# PIBSchematic.net
KiCad netlist of a schematic drawn in Altium Designer
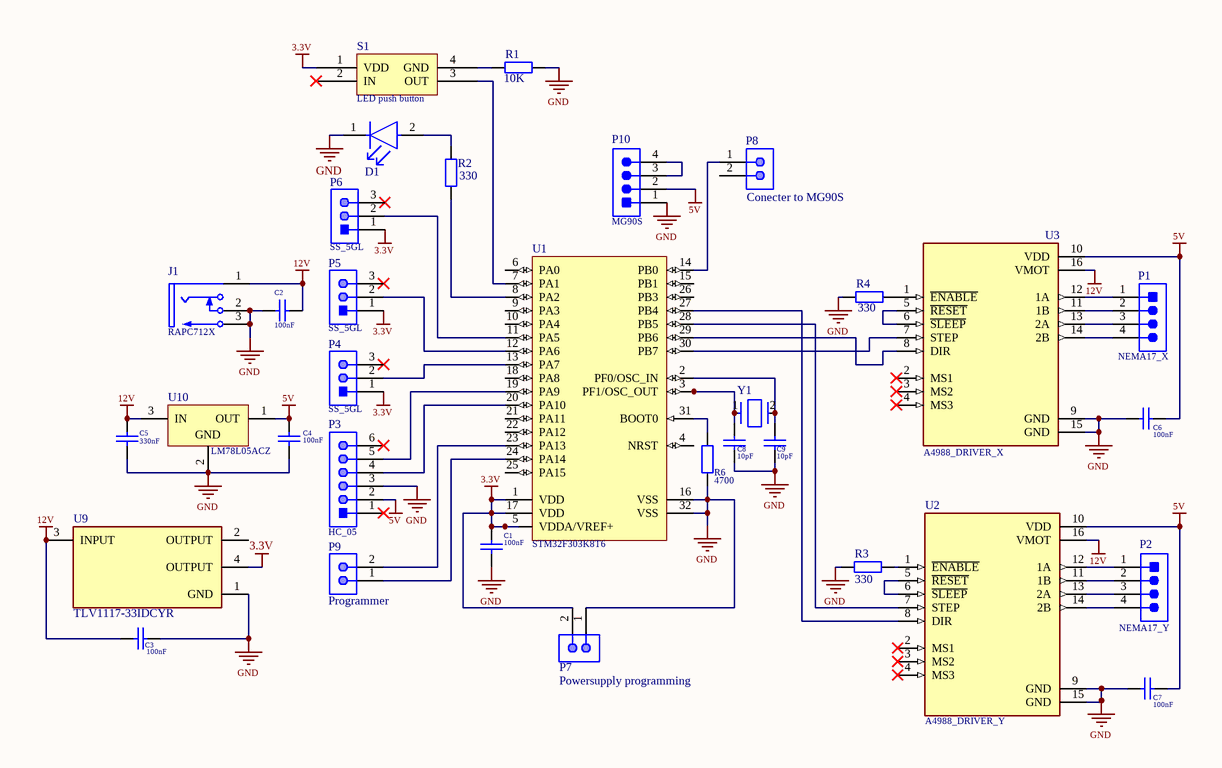
[diagram p0: PIBSchematic.SchDoc]

(export (version "E")
  (design (tool "Eeschema 10.0.6"))
  (components
    (comp (ref "C1")
      (value "100nF")
      (footprint "KEMT-1206-2_M")
      (description "CAP, Ceramic, 0.1 uF, +/- 10%, 50 V, -55 to 125 degC, 1206 (3216 Metric), RoHS, Tape and Reel")
      (fields (field (name "MANUFACTURER") "Kemet"))
      (libsource (lib "Altium Content Vault") (part "CAP-NP-2"))
    )
    (comp (ref "C2")
      (value "100nF")
      (footprint "KEMT-1206-2_M")
      (description "CAP, Ceramic, 0.1 uF, +/- 10%, 50 V, -55 to 125 degC, 1206 (3216 Metric), RoHS, Tape and Reel")
      (fields (field (name "MANUFACTURER") "Kemet"))
      (libsource (lib "Altium Content Vault") (part "CAP-NP-2"))
    )
    (comp (ref "C3")
      (value "100nF")
      (footprint "KEMT-1206-2_M")
      (description "CAP, Ceramic, 0.1 uF, +/- 10%, 50 V, -55 to 125 degC, 1206 (3216 Metric), RoHS, Tape and Reel")
      (fields (field (name "MANUFACTURER") "Kemet"))
      (libsource (lib "Altium Content Vault") (part "CAP-NP-2"))
    )
    (comp (ref "C4")
      (value "100nF")
      (footprint "KEMT-1206-2_M")
      (description "CAP, Ceramic, 0.1 uF, +/- 10%, 50 V, -55 to 125 degC, 1206 (3216 Metric), RoHS, Tape and Reel")
      (fields (field (name "MANUFACTURER") "Kemet"))
      (libsource (lib "Altium Content Vault") (part "CAP-NP-2"))
    )
    (comp (ref "C5")
      (value "330nF")
      (footprint "KEMT-1206-2_M")
      (description "CAP, Ceramic, 0.1 uF, +/- 10%, 50 V, -55 to 125 degC, 1206 (3216 Metric), RoHS, Tape and Reel")
      (fields (field (name "MANUFACTURER") "Kemet"))
      (libsource (lib "Altium Content Vault") (part "CAP-NP-2"))
    )
    (comp (ref "C6")
      (value "100nF")
      (footprint "KEMT-1206-2_M")
      (description "CAP, Ceramic, 0.1 uF, +/- 10%, 50 V, -55 to 125 degC, 1206 (3216 Metric), RoHS, Tape and Reel")
      (fields (field (name "MANUFACTURER") "Kemet"))
      (libsource (lib "Altium Content Vault") (part "CAP-NP-2"))
    )
    (comp (ref "C7")
      (value "100nF")
      (footprint "KEMT-1206-2_M")
      (description "CAP, Ceramic, 0.1 uF, +/- 10%, 50 V, -55 to 125 degC, 1206 (3216 Metric), RoHS, Tape and Reel")
      (fields (field (name "MANUFACTURER") "Kemet"))
      (libsource (lib "Altium Content Vault") (part "CAP-NP-2"))
    )
    (comp (ref "C8")
      (value "10pF")
      (footprint "KEMT-1206-2_M")
      (description "CAP, Ceramic, 0.1 uF, +/- 10%, 50 V, -55 to 125 degC, 1206 (3216 Metric), RoHS, Tape and Reel")
      (fields (field (name "MANUFACTURER") "Kemet"))
      (libsource (lib "Altium Content Vault") (part "CAP-NP-2"))
    )
    (comp (ref "C9")
      (value "10pF")
      (footprint "KEMT-1206-2_M")
      (description "CAP, Ceramic, 0.1 uF, +/- 10%, 50 V, -55 to 125 degC, 1206 (3216 Metric), RoHS, Tape and Reel")
      (fields (field (name "MANUFACTURER") "Kemet"))
      (libsource (lib "Altium Content Vault") (part "CAP-NP-2"))
    )
    (comp (ref "D1")
      (value "HLMP-1719")
      (footprint "FP-HLMP-1719-MFG")
      (description "LED YELLOW DIFFUSED T-1 T/H")
      (fields
        (field (name "MANUFACTURER") "Broadcom")
        (field (name "OCTOPART") "https://octopart.com/hlmp-1719-broadcom-71130405")
      )
      (libsource (lib "Altium Content Vault") (part "8706943c75ba83719d021d2fdc84c58"))
    )
    (comp (ref "J1")
      (value "RAPC712X")
      (footprint "SWITCH-RAPC712X-3_V")
      (description "Conn Powerjack Mini R/A PCMT, 5 A, 3-Pin THD, RoHS")
      (fields (field (name "MANUFACTURER") "Switchcraft"))
      (libsource (lib "Altium Content Vault") (part "SWITCH-RAPC712X-3"))
    )
    (comp (ref "P1")
      (value "NEMA17_X")
      (footprint "TECO-640456-4")
      (description "Male Header, Pitch 2.54 mm, 1 x 4 Position, Height 10.03 mm, Tail Length 3.56 mm, RoHS, Bulk")
      (fields (field (name "MANUFACTURER") "TE Connectivity"))
      (libsource (lib "Altium Content Vault") (part "CN-1P-M-R4"))
    )
    (comp (ref "P2")
      (value "NEMA17_Y")
      (footprint "TECO-640456-4")
      (description "Male Header, Pitch 2.54 mm, 1 x 4 Position, Height 10.03 mm, Tail Length 3.56 mm, RoHS, Bulk")
      (fields (field (name "MANUFACTURER") "TE Connectivity"))
      (libsource (lib "Altium Content Vault") (part "CN-1P-M-R4"))
    )
    (comp (ref "P3")
      (value "HC_05")
      (footprint "66200611122")
      (description "THT Male Header WR-MPC3, Vertical, Single Row, pitch 3 mm, 6 pins")
      (fields
        (field (name "MANUFACTURER") "Wurth Elektronik")
        (field (name "PART NUMBER") "66200611122")
        (field (name "PUBLISHER") "WurthElektronik")
      )
      (libsource (lib "Altium Content Vault") (part "WE-CN-1P-M-R6"))
    )
    (comp (ref "P4")
      (value "SS_5GL")
      (footprint "66200311122")
      (description "THT Male Header WR-MPC3, Vertical, Single Row, pitch 3 mm, 3 pins")
      (fields
        (field (name "MANUFACTURER") "Wurth Elektronik")
        (field (name "PART NUMBER") "66200311122")
        (field (name "PUBLISHER") "WurthElektronik")
      )
      (libsource (lib "Altium Content Vault") (part "WE-CN-1P-M-R3"))
    )
    (comp (ref "P5")
      (value "SS_5GL")
      (footprint "66200311122")
      (description "THT Male Header WR-MPC3, Vertical, Single Row, pitch 3 mm, 3 pins")
      (fields
        (field (name "MANUFACTURER") "Wurth Elektronik")
        (field (name "PART NUMBER") "66200311122")
        (field (name "PUBLISHER") "WurthElektronik")
      )
      (libsource (lib "Altium Content Vault") (part "WE-CN-1P-M-R3"))
    )
    (comp (ref "P6")
      (value "SS_5GL")
      (footprint "66200311122")
      (description "THT Male Header WR-MPC3, Vertical, Single Row, pitch 3 mm, 3 pins")
      (fields
        (field (name "MANUFACTURER") "Wurth Elektronik")
        (field (name "PART NUMBER") "66200311122")
        (field (name "PUBLISHER") "WurthElektronik")
      )
      (libsource (lib "Altium Content Vault") (part "WE-CN-1P-M-R3"))
    )
    (comp (ref "P7")
      (value "Powersupply programming")
      (footprint "TECO-5-146280-2_V")
      (fields (field (name "MANUFACTURER") "TE Connectivity"))
      (libsource (lib "Altium Content Vault") (part "CN-1P-M-R2"))
    )
    (comp (ref "P8")
      (value "Conecter to MG90S")
      (footprint "TECO-5-146280-2_V")
      (fields (field (name "MANUFACTURER") "TE Connectivity"))
      (libsource (lib "") (part "CN-1P-M-R2_1"))
    )
    (comp (ref "P9")
      (value "Programmer")
      (footprint "TECO-5-146280-2_V")
      (fields (field (name "MANUFACTURER") "TE Connectivity"))
      (libsource (lib "") (part "CN-1P-M-R2_2"))
    )
    (comp (ref "P10")
      (value "MG90S")
      (footprint "TECO-640456-4")
      (description "Male Header, Pitch 2.54 mm, 1 x 4 Position, Height 10.03 mm, Tail Length 3.56 mm, RoHS, Bulk")
      (fields (field (name "MANUFACTURER") "TE Connectivity"))
      (libsource (lib "") (part "CN-1P-M-R4_1"))
    )
    (comp (ref "R1")
      (value "10K")
      (footprint "AXIAL-0.4")
      (description "Resistor")
      (fields (field (name "Comment") "Res2") (field (name "PUBLISHER") "Altium Limited"))
      (libsource (lib "") (part "Res2_1"))
    )
    (comp (ref "R2")
      (value "330")
      (footprint "AXIAL-0.4")
      (description "Resistor")
      (fields (field (name "Comment") "Res2") (field (name "PUBLISHER") "Altium Limited"))
      (libsource (lib "Miscellaneous Devices") (part "Res2"))
    )
    (comp (ref "R3")
      (value "330")
      (footprint "AXIAL-0.4")
      (description "Resistor")
      (fields (field (name "Comment") "Res2") (field (name "PUBLISHER") "Altium Limited"))
      (libsource (lib "") (part "Res2_1"))
    )
    (comp (ref "R4")
      (value "330")
      (footprint "AXIAL-0.4")
      (description "Resistor")
      (fields (field (name "Comment") "Res2") (field (name "PUBLISHER") "Altium Limited"))
      (libsource (lib "") (part "Res2_1"))
    )
    (comp (ref "R6")
      (value "4700")
      (footprint "AXIAL-0.4")
      (description "Resistor")
      (fields (field (name "Comment") "Res2") (field (name "PUBLISHER") "Altium Limited"))
      (libsource (lib "Miscellaneous Devices") (part "Res2"))
    )
    (comp (ref "S1")
      (value "LED push button")
      (footprint "LED push button PcbLib1:PCBComponent_1")
      (libsource (lib "LED push button") (part "LED push button"))
    )
    (comp (ref "U1")
      (value "STM32F303K8T6")
      (footprint "STM-LQFP32_M")
      (libsource (lib "Altium Content Vault") (part "MC-ARM-STM32F303-LQFP32"))
    )
    (comp (ref "U2")
      (value "A4988_DRIVER_Y")
      (footprint "MODULE_A4988_STEPPER_MOTOR_DRIVER_CARRIER")
      (description "Stepper Motor Driver")
      (fields (field (name "MP") "A4988 STEPPER MOTOR DRIVER CARRIER") (field (name "MF") "Pololu"))
      (libsource (lib "A4988_STEPPER_MOTOR_DRIVER_CARRIER") (part "A4988_STEPPER_MOTOR_DRIVER_CARRIER"))
    )
    (comp (ref "U3")
      (value "A4988_DRIVER_X")
      (footprint "MODULE_A4988_STEPPER_MOTOR_DRIVER_CARRIER")
      (description "Stepper Motor Driver")
      (fields (field (name "MP") "A4988 STEPPER MOTOR DRIVER CARRIER") (field (name "MF") "Pololu"))
      (libsource (lib "A4988_STEPPER_MOTOR_DRIVER_CARRIER") (part "A4988_STEPPER_MOTOR_DRIVER_CARRIER"))
    )
    (comp (ref "U9")
      (value "TLV1117-33IDCYR")
      (footprint "FP-DCY0004A-MFG")
      (description "IC REG LIN 3.3V 800MA SOT223-4")
      (fields
        (field (name "MANUFACTURER") "Texas Instruments")
        (field (name "OCTOPART") "https://octopart.com/tlv1117-33idcyr-texas+instruments-669250")
      )
      (libsource (lib "Altium Content Vault") (part "d420fb9686013fb832e66295cdf4acf"))
    )
    (comp (ref "U10")
      (value "LM78L05ACZ")
      (footprint "LP0003A")
      (description "3-Terminal Positive Regulator, 5 Vout, 3-pin TO-92, Pb-Free")
      (fields (field (name "PARTNUMBER") "LM78L05ACZ/NOPB") (field (name "MANUFACTURER") "Texas Instruments"))
      (libsource (lib "Altium Content Vault") (part "PM-REG-LM78L05-SIL3"))
    )
    (comp (ref "Y1")
      (value "ABLS2-8.000MHZ-D4Y-T")
      (footprint "FP-ABLS2-MFG")
      (description "CRYSTAL 8.0000MHZ 18PF SMD")
      (fields (field (name "TOLERANCE") "30ppm"))
      (libsource (lib "Altium Content Vault") (part "c23a69dc6c9e2f18f2079038eb95dd1"))
    )
  )
  (nets
    (net (code "1") (name "3.3V") (class "Default")
      (node (ref "C1") (pin "2") (pinfunction "2_2") (pintype "passive"))
      (node (ref "P4") (pin "1") (pinfunction "1_1") (pintype "passive"))
      (node (ref "P5") (pin "1") (pinfunction "1_1") (pintype "passive"))
      (node (ref "P6") (pin "1") (pinfunction "1_1") (pintype "passive"))
      (node (ref "P7") (pin "2") (pinfunction "2_2") (pintype "passive"))
      (node (ref "S1") (pin "1") (pinfunction "VDD_1") (pintype "passive"))
      (node (ref "U1") (pin "1") (pinfunction "VDD_1") (pintype "power_in"))
      (node (ref "U1") (pin "17") (pinfunction "VDD_17") (pintype "power_in"))
      (node (ref "U1") (pin "5") (pinfunction "VDDA/VREF+_5") (pintype "power_in"))
      (node (ref "U9") (pin "4") (pinfunction "OUTPUT_4") (pintype "power_in"))
    )
    (net (code "2") (name "5V") (class "Default")
      (node (ref "C4") (pin "1") (pinfunction "1_1") (pintype "passive"))
      (node (ref "C6") (pin "1") (pinfunction "1_1") (pintype "passive"))
      (node (ref "C7") (pin "1") (pinfunction "1_1") (pintype "passive"))
      (node (ref "P10") (pin "2") (pinfunction "2_2") (pintype "passive"))
      (node (ref "P3") (pin "2") (pinfunction "2_2") (pintype "passive"))
      (node (ref "U10") (pin "1") (pinfunction "OUT_1") (pintype "power_in"))
      (node (ref "U2") (pin "10") (pinfunction "VDD_10") (pintype "power_in"))
      (node (ref "U3") (pin "10") (pinfunction "VDD_10") (pintype "power_in"))
    )
    (net (code "3") (name "12V") (class "Default")
      (node (ref "C2") (pin "2") (pinfunction "2_2") (pintype "passive"))
      (node (ref "C3") (pin "2") (pinfunction "2_2") (pintype "passive"))
      (node (ref "C5") (pin "2") (pinfunction "2_2") (pintype "passive"))
      (node (ref "J1") (pin "1") (pinfunction "1_1") (pintype "passive"))
      (node (ref "U10") (pin "3") (pinfunction "IN_3") (pintype "power_in"))
      (node (ref "U2") (pin "16") (pinfunction "VMOT_16") (pintype "power_in"))
      (node (ref "U3") (pin "16") (pinfunction "VMOT_16") (pintype "power_in"))
      (node (ref "U9") (pin "3") (pinfunction "INPUT_3") (pintype "power_in"))
    )
    (net (code "4") (name "GND") (class "Default")
      (node (ref "C1") (pin "1") (pinfunction "1_1") (pintype "passive"))
      (node (ref "C2") (pin "1") (pinfunction "1_1") (pintype "passive"))
      (node (ref "C3") (pin "1") (pinfunction "1_1") (pintype "passive"))
      (node (ref "C4") (pin "2") (pinfunction "2_2") (pintype "passive"))
      (node (ref "C5") (pin "1") (pinfunction "1_1") (pintype "passive"))
      (node (ref "C6") (pin "2") (pinfunction "2_2") (pintype "passive"))
      (node (ref "C7") (pin "2") (pinfunction "2_2") (pintype "passive"))
      (node (ref "C8") (pin "2") (pinfunction "2_2") (pintype "passive"))
      (node (ref "C9") (pin "2") (pinfunction "2_2") (pintype "passive"))
      (node (ref "D1") (pin "1") (pinfunction "C_1") (pintype "passive"))
      (node (ref "J1") (pin "2") (pinfunction "2_2") (pintype "passive"))
      (node (ref "J1") (pin "3") (pinfunction "3_3") (pintype "passive"))
      (node (ref "P10") (pin "1") (pinfunction "1_1") (pintype "passive"))
      (node (ref "P3") (pin "3") (pinfunction "3_3") (pintype "passive"))
      (node (ref "P7") (pin "1") (pinfunction "1_1") (pintype "passive"))
      (node (ref "R1") (pin "2") (pinfunction "2_2") (pintype "passive"))
      (node (ref "R3") (pin "1") (pinfunction "1_1") (pintype "passive"))
      (node (ref "R4") (pin "1") (pinfunction "1_1") (pintype "passive"))
      (node (ref "R6") (pin "1") (pinfunction "1_1") (pintype "passive"))
      (node (ref "U1") (pin "16") (pinfunction "VSS_16") (pintype "power_in"))
      (node (ref "U1") (pin "32") (pinfunction "VSS_32") (pintype "power_in"))
      (node (ref "U10") (pin "2") (pinfunction "GND_2") (pintype "power_in"))
      (node (ref "U2") (pin "15") (pinfunction "GND_15") (pintype "power_in"))
      (node (ref "U2") (pin "9") (pinfunction "GND_9") (pintype "power_in"))
      (node (ref "U3") (pin "15") (pinfunction "GND_15") (pintype "power_in"))
      (node (ref "U3") (pin "9") (pinfunction "GND_9") (pintype "power_in"))
      (node (ref "U9") (pin "1") (pinfunction "GND_1") (pintype "power_in"))
    )
    (net (code "5") (name "Net-(D1-A)") (class "Default")
      (node (ref "D1") (pin "2") (pinfunction "A_2") (pintype "passive"))
      (node (ref "R2") (pin "2") (pinfunction "2_2") (pintype "passive"))
    )
    (net (code "6") (name "Net-(P10-Pad3)") (class "Default")
      (node (ref "P10") (pin "3") (pinfunction "3_3") (pintype "passive"))
      (node (ref "P10") (pin "4") (pinfunction "4_4") (pintype "passive"))
    )
    (net (code "7") (name "Net-(S1-GND)") (class "Default")
      (node (ref "R1") (pin "1") (pinfunction "1_1") (pintype "passive"))
      (node (ref "S1") (pin "4") (pinfunction "GND_4") (pintype "passive"))
    )
    (net (code "8") (name "Net-(S1-OUT)") (class "Default")
      (node (ref "S1") (pin "3") (pinfunction "OUT_3") (pintype "passive"))
      (node (ref "U1") (pin "7") (pinfunction "PA1_7") (pintype "bidirectional"))
    )
    (net (code "9") (name "Net-(U1-BOOT0)") (class "Default")
      (node (ref "R6") (pin "2") (pinfunction "2_2") (pintype "passive"))
      (node (ref "U1") (pin "31") (pinfunction "BOOT0_31") (pintype "input"))
    )
    (net (code "10") (name "Net-(U1-PA2)") (class "Default")
      (node (ref "R2") (pin "1") (pinfunction "1_1") (pintype "passive"))
      (node (ref "U1") (pin "8") (pinfunction "PA2_8") (pintype "bidirectional"))
    )
    (net (code "11") (name "Net-(U1-PA5)") (class "Default")
      (node (ref "P6") (pin "2") (pinfunction "2_2") (pintype "passive"))
      (node (ref "U1") (pin "11") (pinfunction "PA5_11") (pintype "bidirectional"))
    )
    (net (code "12") (name "Net-(U1-PA6)") (class "Default")
      (node (ref "P5") (pin "2") (pinfunction "2_2") (pintype "passive"))
      (node (ref "U1") (pin "12") (pinfunction "PA6_12") (pintype "bidirectional"))
    )
    (net (code "13") (name "Net-(U1-PA7)") (class "Default")
      (node (ref "P4") (pin "2") (pinfunction "2_2") (pintype "passive"))
      (node (ref "U1") (pin "13") (pinfunction "PA7_13") (pintype "bidirectional"))
    )
    (net (code "14") (name "Net-(U1-PA9)") (class "Default")
      (node (ref "P3") (pin "5") (pinfunction "5_5") (pintype "passive"))
      (node (ref "U1") (pin "19") (pinfunction "PA9_19") (pintype "bidirectional"))
    )
    (net (code "15") (name "Net-(U1-PA10)") (class "Default")
      (node (ref "P3") (pin "4") (pinfunction "4_4") (pintype "passive"))
      (node (ref "U1") (pin "20") (pinfunction "PA10_20") (pintype "bidirectional"))
    )
    (net (code "16") (name "Net-(U1-PA13)") (class "Default")
      (node (ref "P9") (pin "2") (pinfunction "2_2") (pintype "passive"))
      (node (ref "U1") (pin "23") (pinfunction "PA13_23") (pintype "bidirectional"))
    )
    (net (code "17") (name "Net-(U1-PA14)") (class "Default")
      (node (ref "P9") (pin "1") (pinfunction "1_1") (pintype "passive"))
      (node (ref "U1") (pin "24") (pinfunction "PA14_24") (pintype "bidirectional"))
    )
    (net (code "18") (name "Net-(U1-PB0)") (class "Default")
      (node (ref "P8") (pin "1") (pinfunction "1_1") (pintype "passive"))
      (node (ref "U1") (pin "14") (pinfunction "PB0_14") (pintype "bidirectional"))
    )
    (net (code "19") (name "Net-(U1-PB4)") (class "Default")
      (node (ref "U1") (pin "27") (pinfunction "PB4_27") (pintype "bidirectional"))
      (node (ref "U2") (pin "8") (pinfunction "DIR_8") (pintype "input"))
    )
    (net (code "20") (name "Net-(U1-PB5)") (class "Default")
      (node (ref "U1") (pin "28") (pinfunction "PB5_28") (pintype "bidirectional"))
      (node (ref "U2") (pin "7") (pinfunction "STEP_7") (pintype "input"))
    )
    (net (code "21") (name "Net-(U1-PB6)") (class "Default")
      (node (ref "U1") (pin "29") (pinfunction "PB6_29") (pintype "bidirectional"))
      (node (ref "U3") (pin "8") (pinfunction "DIR_8") (pintype "input"))
    )
    (net (code "22") (name "Net-(U1-PB7)") (class "Default")
      (node (ref "U1") (pin "30") (pinfunction "PB7_30") (pintype "bidirectional"))
      (node (ref "U3") (pin "7") (pinfunction "STEP_7") (pintype "input"))
    )
    (net (code "23") (name "Net-(U1-PF0{slash}OSC_IN)") (class "Default")
      (node (ref "C9") (pin "1") (pinfunction "1_1") (pintype "passive"))
      (node (ref "U1") (pin "2") (pinfunction "PF0/OSC_IN_2") (pintype "bidirectional"))
      (node (ref "Y1") (pin "2") (pinfunction "2_2") (pintype "passive"))
    )
    (net (code "24") (name "Net-(U1-PF1{slash}OSC_OUT)") (class "Default")
      (node (ref "C8") (pin "1") (pinfunction "1_1") (pintype "passive"))
      (node (ref "U1") (pin "3") (pinfunction "PF1/OSC_OUT_3") (pintype "bidirectional"))
      (node (ref "Y1") (pin "1") (pinfunction "1_1") (pintype "passive"))
    )
    (net (code "25") (name "Net-(U2-1A)") (class "Default")
      (node (ref "P2") (pin "1") (pinfunction "1_1") (pintype "passive"))
      (node (ref "U2") (pin "12") (pinfunction "1A_12") (pintype "output"))
    )
    (net (code "26") (name "Net-(U2-1B)") (class "Default")
      (node (ref "P2") (pin "2") (pinfunction "2_2") (pintype "passive"))
      (node (ref "U2") (pin "11") (pinfunction "1B_11") (pintype "output"))
    )
    (net (code "27") (name "Net-(U2-2A)") (class "Default")
      (node (ref "P2") (pin "3") (pinfunction "3_3") (pintype "passive"))
      (node (ref "U2") (pin "13") (pinfunction "2A_13") (pintype "output"))
    )
    (net (code "28") (name "Net-(U2-2B)") (class "Default")
      (node (ref "P2") (pin "4") (pinfunction "4_4") (pintype "passive"))
      (node (ref "U2") (pin "14") (pinfunction "2B_14") (pintype "output"))
    )
    (net (code "29") (name "Net-(U2-~{ENABLE})") (class "Default")
      (node (ref "R3") (pin "2") (pinfunction "2_2") (pintype "passive"))
      (node (ref "U2") (pin "1") (pinfunction "~{ENABLE}_1") (pintype "input"))
    )
    (net (code "30") (name "Net-(U2-~{RESET})") (class "Default")
      (node (ref "U2") (pin "5") (pinfunction "~{RESET}_5") (pintype "input"))
      (node (ref "U2") (pin "6") (pinfunction "~{SLEEP}_6") (pintype "input"))
    )
    (net (code "31") (name "Net-(U3-1A)") (class "Default")
      (node (ref "P1") (pin "1") (pinfunction "1_1") (pintype "passive"))
      (node (ref "U3") (pin "12") (pinfunction "1A_12") (pintype "output"))
    )
    (net (code "32") (name "Net-(U3-1B)") (class "Default")
      (node (ref "P1") (pin "2") (pinfunction "2_2") (pintype "passive"))
      (node (ref "U3") (pin "11") (pinfunction "1B_11") (pintype "output"))
    )
    (net (code "33") (name "Net-(U3-2A)") (class "Default")
      (node (ref "P1") (pin "3") (pinfunction "3_3") (pintype "passive"))
      (node (ref "U3") (pin "13") (pinfunction "2A_13") (pintype "output"))
    )
    (net (code "34") (name "Net-(U3-2B)") (class "Default")
      (node (ref "P1") (pin "4") (pinfunction "4_4") (pintype "passive"))
      (node (ref "U3") (pin "14") (pinfunction "2B_14") (pintype "output"))
    )
    (net (code "35") (name "Net-(U3-~{ENABLE})") (class "Default")
      (node (ref "R4") (pin "2") (pinfunction "2_2") (pintype "passive"))
      (node (ref "U3") (pin "1") (pinfunction "~{ENABLE}_1") (pintype "input"))
    )
    (net (code "36") (name "Net-(U3-~{RESET})") (class "Default")
      (node (ref "U3") (pin "5") (pinfunction "~{RESET}_5") (pintype "input"))
      (node (ref "U3") (pin "6") (pinfunction "~{SLEEP}_6") (pintype "input"))
    )
    (net (code "37") (name "unconnected-(P3-Pad1)") (class "Default")
      (node (ref "P3") (pin "1") (pinfunction "1_1") (pintype "passive+no_connect"))
    )
    (net (code "38") (name "unconnected-(P3-Pad6)") (class "Default")
      (node (ref "P3") (pin "6") (pinfunction "6_6") (pintype "passive+no_connect"))
    )
    (net (code "39") (name "unconnected-(P4-Pad3)") (class "Default")
      (node (ref "P4") (pin "3") (pinfunction "3_3") (pintype "passive+no_connect"))
    )
    (net (code "40") (name "unconnected-(P5-Pad3)") (class "Default")
      (node (ref "P5") (pin "3") (pinfunction "3_3") (pintype "passive+no_connect"))
    )
    (net (code "41") (name "unconnected-(P6-Pad3)") (class "Default")
      (node (ref "P6") (pin "3") (pinfunction "3_3") (pintype "passive+no_connect"))
    )
    (net (code "42") (name "unconnected-(P8-Pad2)") (class "Default")
      (node (ref "P8") (pin "2") (pinfunction "2_2") (pintype "passive"))
    )
    (net (code "43") (name "unconnected-(S1-IN-Pad2)") (class "Default")
      (node (ref "S1") (pin "2") (pinfunction "IN_2") (pintype "passive+no_connect"))
    )
    (net (code "44") (name "unconnected-(U1-NRST-Pad4)") (class "Default")
      (node (ref "U1") (pin "4") (pinfunction "NRST_4") (pintype "bidirectional"))
    )
    (net (code "45") (name "unconnected-(U1-PA0-Pad6)") (class "Default")
      (node (ref "U1") (pin "6") (pinfunction "PA0_6") (pintype "bidirectional"))
    )
    (net (code "46") (name "unconnected-(U1-PA3-Pad9)") (class "Default")
      (node (ref "U1") (pin "9") (pinfunction "PA3_9") (pintype "bidirectional"))
    )
    (net (code "47") (name "unconnected-(U1-PA4-Pad10)") (class "Default")
      (node (ref "U1") (pin "10") (pinfunction "PA4_10") (pintype "bidirectional"))
    )
    (net (code "48") (name "unconnected-(U1-PA8-Pad18)") (class "Default")
      (node (ref "U1") (pin "18") (pinfunction "PA8_18") (pintype "bidirectional"))
    )
    (net (code "49") (name "unconnected-(U1-PA11-Pad21)") (class "Default")
      (node (ref "U1") (pin "21") (pinfunction "PA11_21") (pintype "bidirectional"))
    )
    (net (code "50") (name "unconnected-(U1-PA12-Pad22)") (class "Default")
      (node (ref "U1") (pin "22") (pinfunction "PA12_22") (pintype "bidirectional"))
    )
    (net (code "51") (name "unconnected-(U1-PA15-Pad25)") (class "Default")
      (node (ref "U1") (pin "25") (pinfunction "PA15_25") (pintype "bidirectional"))
    )
    (net (code "52") (name "unconnected-(U1-PB1-Pad15)") (class "Default")
      (node (ref "U1") (pin "15") (pinfunction "PB1_15") (pintype "bidirectional"))
    )
    (net (code "53") (name "unconnected-(U1-PB3-Pad26)") (class "Default")
      (node (ref "U1") (pin "26") (pinfunction "PB3_26") (pintype "bidirectional"))
    )
    (net (code "54") (name "unconnected-(U2-MS1-Pad2)") (class "Default")
      (node (ref "U2") (pin "2") (pinfunction "MS1_2") (pintype "input+no_connect"))
    )
    (net (code "55") (name "unconnected-(U2-MS2-Pad3)") (class "Default")
      (node (ref "U2") (pin "3") (pinfunction "MS2_3") (pintype "input+no_connect"))
    )
    (net (code "56") (name "unconnected-(U2-MS3-Pad4)") (class "Default")
      (node (ref "U2") (pin "4") (pinfunction "MS3_4") (pintype "input+no_connect"))
    )
    (net (code "57") (name "unconnected-(U3-MS1-Pad2)") (class "Default")
      (node (ref "U3") (pin "2") (pinfunction "MS1_2") (pintype "input+no_connect"))
    )
    (net (code "58") (name "unconnected-(U3-MS2-Pad3)") (class "Default")
      (node (ref "U3") (pin "3") (pinfunction "MS2_3") (pintype "input+no_connect"))
    )
    (net (code "59") (name "unconnected-(U3-MS3-Pad4)") (class "Default")
      (node (ref "U3") (pin "4") (pinfunction "MS3_4") (pintype "input+no_connect"))
    )
    (net (code "60") (name "unconnected-(U9-OUTPUT-Pad2)") (class "Default")
      (node (ref "U9") (pin "2") (pinfunction "OUTPUT_2") (pintype "power_in"))
    )
  )
)
